# MAGNETOMETER.net
KiCad netlist of a schematic drawn in Altium Designer
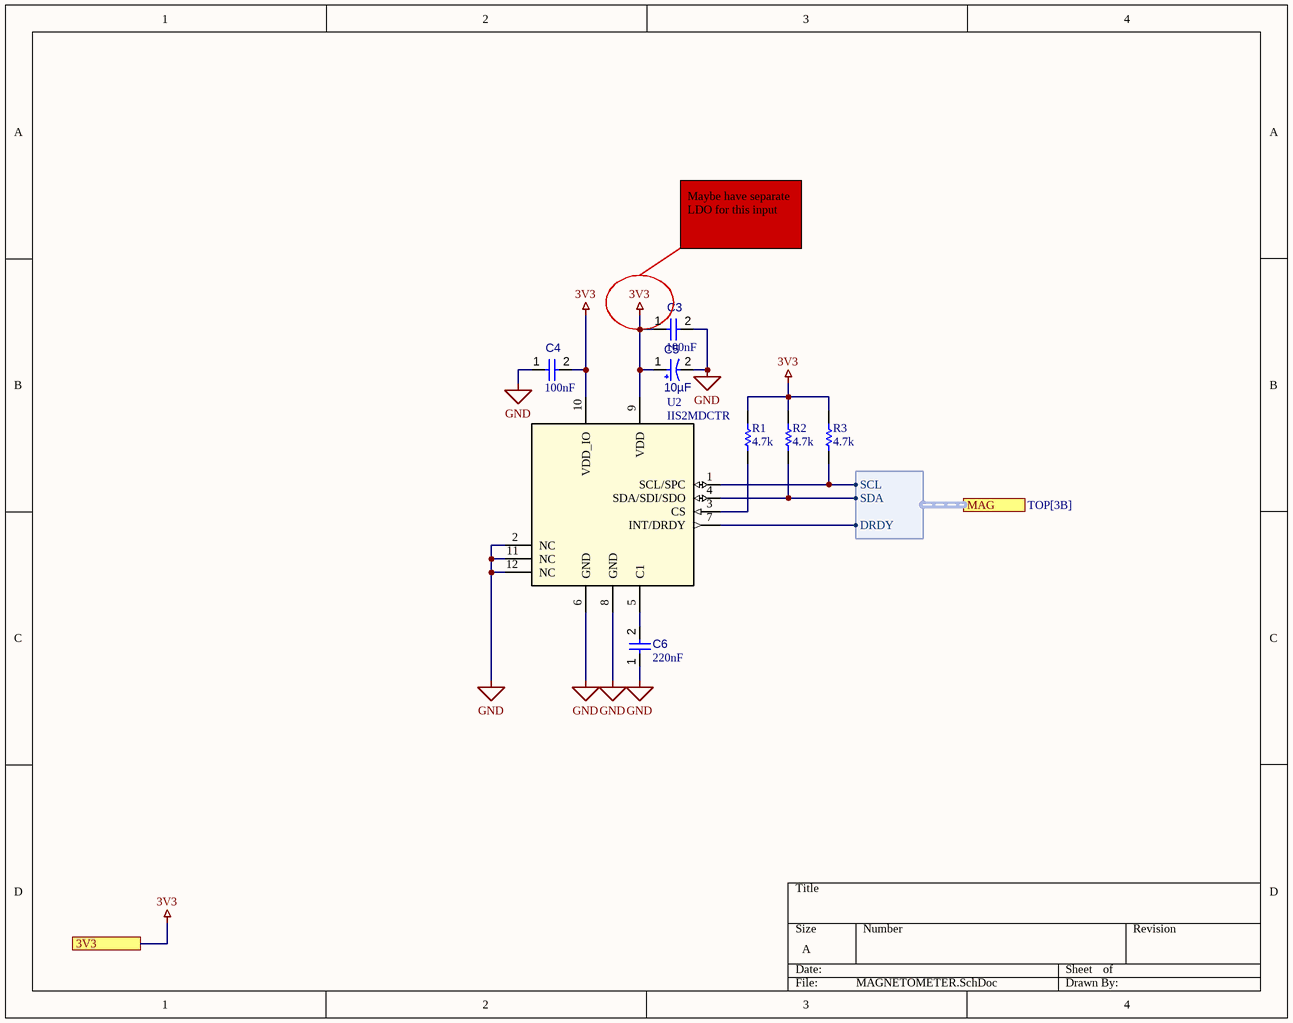
[diagram p0: MAGNETOMETER.SchDoc]

(export (version "E")
  (design (tool "Eeschema 10.0.6"))
  (components
    (comp (ref "C3")
      (value "100nF")
      (footprint "CAPC1005X56X25LL10T15")
      (description "Chip Capacitor, 0.1 uF, +/- 5%, 16 V, 0402 (1005 Metric)")
      (fields (field (name "TOLERANCE") "5%") (field (name "Comment") "Capacitor 0.1 uF +/- 5% 16 V 0402"))
      (libsource (lib "Altium Default Library") (part "CAP-NP-2"))
    )
    (comp (ref "C4")
      (value "100nF")
      (footprint "CAPC1005X56X25LL10T15")
      (description "Chip Capacitor, 0.1 uF, +/- 5%, 16 V, 0402 (1005 Metric)")
      (fields (field (name "TOLERANCE") "5%") (field (name "Comment") "Capacitor 0.1 uF +/- 5% 16 V 0402"))
      (libsource (lib "Altium Default Library") (part "CAP-NP-2"))
    )
    (comp (ref "C5") (value "10µF") (libsource (lib "Altium Default Library") (part "CAP-P-2")))
    (comp (ref "C6")
      (value "220nF")
      (footprint "CAPC0402(1005)60_L")
      (description "Chip Capacitor, 220nF +/-20%, 10V, 0402, Thickness 0.6 mm")
      (fields (field (name "TOLERANCE") "10%") (field (name "Comment") "Capacitor 220nF +/-20% 10V 0402"))
      (libsource (lib "Altium Default Library") (part "CAP-NP-2"))
    )
    (comp (ref "R1")
      (value "4.7k")
      (footprint "RESC1005X40X25ML05T05")
      (description "Chip Resistor, 4.7 KOhm, +/- 1%, 0.1 W, -55 to 155 degC, 0402 (1005 Metric)")
      (fields (field (name "POWER") "100mW") (field (name "TOLERANCE") "1%"))
      (libsource (lib "Altium Default Library") (part "RES-2"))
    )
    (comp (ref "R2")
      (value "4.7k")
      (footprint "RESC1005X40X25ML05T05")
      (description "Chip Resistor, 4.7 KOhm, +/- 1%, 0.1 W, -55 to 155 degC, 0402 (1005 Metric)")
      (fields (field (name "POWER") "100mW") (field (name "TOLERANCE") "1%"))
      (libsource (lib "Altium Default Library") (part "RES-2"))
    )
    (comp (ref "R3")
      (value "4.7k")
      (footprint "RESC1005X40X25ML05T05")
      (description "Chip Resistor, 4.7 KOhm, +/- 1%, 0.1 W, -55 to 155 degC, 0402 (1005 Metric)")
      (fields (field (name "POWER") "100mW") (field (name "TOLERANCE") "1%"))
      (libsource (lib "Altium Default Library") (part "RES-2"))
    )
    (comp (ref "U2")
      (value "IIS2MDCTR")
      (footprint "LGA-12_2X2X0P7_STM")
      (description "No Description Available")
      (fields (field (name "COPYRIGHT") "Copyright (C) 2022 Ultra Librarian. All rights reserved."))
      (libsource (lib "IIS2MDCTR") (part "IIS2MDCTR"))
    )
  )
  (nets
    (net (code "2") (name "/DRDY") (class "Default")
      (node (ref "U2") (pin "7") (pinfunction "INT/DRDY_7") (pintype "output"))
    )
    (net (code "3") (name "/SCL") (class "Default")
      (node (ref "R3") (pin "1") (pinfunction "1_1") (pintype "passive"))
      (node (ref "U2") (pin "1") (pinfunction "SCL/SPC_1") (pintype "bidirectional"))
    )
    (net (code "4") (name "/SDA") (class "Default")
      (node (ref "R2") (pin "1") (pinfunction "1_1") (pintype "passive"))
      (node (ref "U2") (pin "4") (pinfunction "SDA/SDI/SDO_4") (pintype "bidirectional"))
    )
    (net (code "6") (name "3V3") (class "Default")
      (node (ref "C3") (pin "1") (pinfunction "1_1") (pintype "passive"))
      (node (ref "C4") (pin "2") (pinfunction "2_2") (pintype "passive"))
      (node (ref "C5") (pin "1") (pinfunction "1_1") (pintype "passive"))
      (node (ref "R1") (pin "2") (pinfunction "2_2") (pintype "passive"))
      (node (ref "R2") (pin "2") (pinfunction "2_2") (pintype "passive"))
      (node (ref "R3") (pin "2") (pinfunction "2_2") (pintype "passive"))
      (node (ref "U2") (pin "10") (pinfunction "VDD_IO_10") (pintype "power_in"))
      (node (ref "U2") (pin "9") (pinfunction "VDD_9") (pintype "power_in"))
    )
    (net (code "7") (name "GND") (class "Default")
      (node (ref "C3") (pin "2") (pinfunction "2_2") (pintype "passive"))
      (node (ref "C4") (pin "1") (pinfunction "1_1") (pintype "passive"))
      (node (ref "C5") (pin "2") (pinfunction "2_2") (pintype "passive"))
      (node (ref "C6") (pin "1") (pinfunction "1_1") (pintype "passive"))
      (node (ref "U2") (pin "11") (pinfunction "NC_11") (pintype "passive"))
      (node (ref "U2") (pin "12") (pinfunction "NC_12") (pintype "passive"))
      (node (ref "U2") (pin "2") (pinfunction "NC_2") (pintype "passive"))
      (node (ref "U2") (pin "6") (pinfunction "GND_6") (pintype "passive"))
      (node (ref "U2") (pin "8") (pinfunction "GND_8") (pintype "passive"))
    )
    (net (code "8") (name "Net-(U2-C1)") (class "Default")
      (node (ref "C6") (pin "2") (pinfunction "2_2") (pintype "passive"))
      (node (ref "U2") (pin "5") (pinfunction "C1_5") (pintype "passive"))
    )
    (net (code "9") (name "Net-(U2-CS)") (class "Default")
      (node (ref "R1") (pin "1") (pinfunction "1_1") (pintype "passive"))
      (node (ref "U2") (pin "3") (pinfunction "CS_3") (pintype "input"))
    )
  )
)
